# TRANSLATOR_8CH.net
KiCad netlist of a schematic drawn in Altium Designer
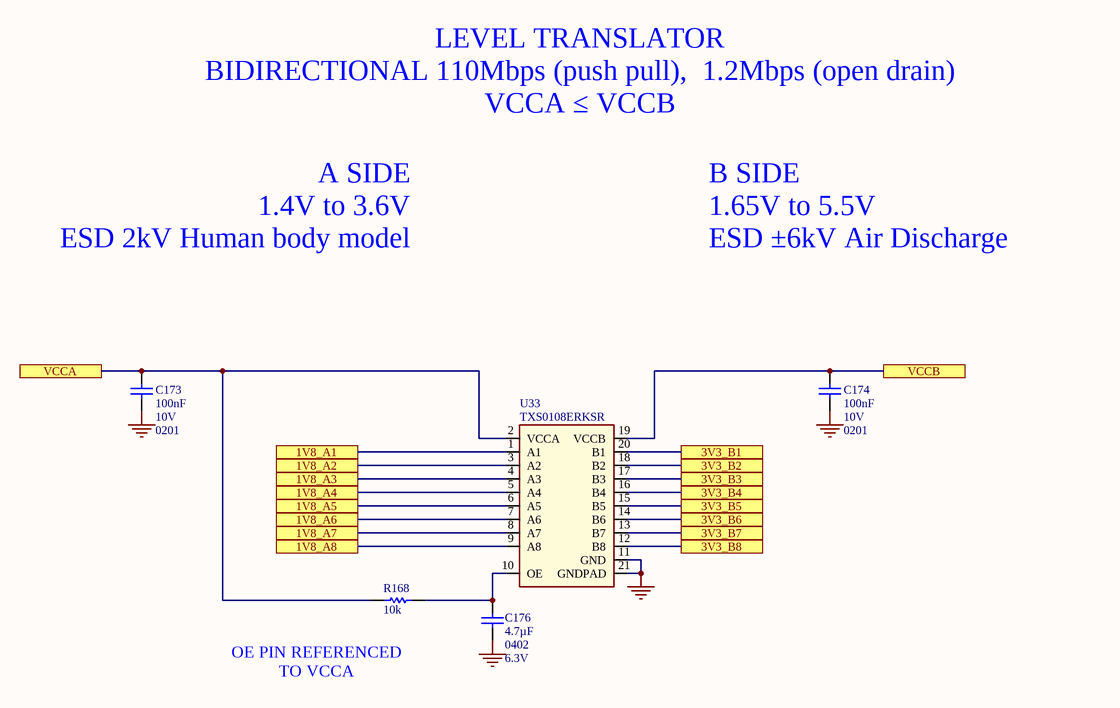
[diagram p0: TRANSLATOR_8CH.SchDoc]

(export (version "E")
  (design (tool "Eeschema 10.0.6"))
  (components
    (comp (ref "C173")
      (value "100nF")
      (footprint "CAP-0201")
      (description "CAP CHIP 0201 100nF 10% 10V X5R")
      (fields
        (field (name "PART NUMBER") "CL03A104KP3NNNC")
        (field (name "MANUFACTURER") "Samsung Electro-Mechanics")
        (field (name "VOLTAGE") "10V")
        (field (name "CASE CODE (IMPERIAL)") "0201")
      )
      (libsource (lib "Clean") (part "CAP"))
    )
    (comp (ref "C174")
      (value "100nF")
      (footprint "CAP-0201")
      (description "CAP CHIP 0201 100nF 10% 10V X5R")
      (fields
        (field (name "PART NUMBER") "CL03A104KP3NNNC")
        (field (name "MANUFACTURER") "Samsung Electro-Mechanics")
        (field (name "VOLTAGE") "10V")
        (field (name "CASE CODE (IMPERIAL)") "0201")
      )
      (libsource (lib "Clean") (part "CAP"))
    )
    (comp (ref "C176")
      (value "4.7µF")
      (footprint "CAP-0402")
      (description "CAP CHIP 0402 4.7uF 20% 6V3 X5R")
      (fields
        (field (name "MANUFACTURER") "Hottech")
        (field (name "PART NUMBER") "C1005A475M6R3NT")
        (field (name "CASE CODE (IMPERIAL)") "0402")
        (field (name "VOLTAGE") "6.3V")
      )
      (libsource (lib "Clean") (part "CAP"))
    )
    (comp (ref "R168")
      (value "10k")
      (footprint "RES-0201")
      (description "RES CHIP 0201 10k 1% 1/20W")
      (fields (field (name "POWER") "50mW") (field (name "TOLERANCE") "1%"))
      (libsource (lib "Clean") (part "RES"))
    )
    (comp (ref "U33")
      (value "TXS0108ERKSR")
      (footprint "QFN50P250X450X100_HS-21N")
      (fields (field (name "MANUFACTURER") "Texas Instruments") (field (name "LCSC PART #") "C43138309"))
      (libsource (lib "Clean") (part "TXS0108ERKSR"))
    )
  )
  (nets
    (net (code "1") (name "/1V8_A1") (class "Default")
      (node (ref "U33") (pin "1") (pinfunction "A1_1") (pintype "power_in"))
    )
    (net (code "2") (name "/1V8_A2") (class "Default")
      (node (ref "U33") (pin "3") (pinfunction "A2_3") (pintype "passive"))
    )
    (net (code "3") (name "/1V8_A3") (class "Default")
      (node (ref "U33") (pin "4") (pinfunction "A3_4") (pintype "power_in"))
    )
    (net (code "4") (name "/1V8_A4") (class "Default")
      (node (ref "U33") (pin "5") (pinfunction "A4_5") (pintype "passive"))
    )
    (net (code "5") (name "/1V8_A5") (class "Default")
      (node (ref "U33") (pin "6") (pinfunction "A5_6") (pintype "passive"))
    )
    (net (code "6") (name "/1V8_A6") (class "Default")
      (node (ref "U33") (pin "7") (pinfunction "A6_7") (pintype "passive"))
    )
    (net (code "7") (name "/1V8_A7") (class "Default")
      (node (ref "U33") (pin "8") (pinfunction "A7_8") (pintype "power_in"))
    )
    (net (code "8") (name "/1V8_A8") (class "Default")
      (node (ref "U33") (pin "9") (pinfunction "A8_9") (pintype "passive"))
    )
    (net (code "9") (name "/3V3_B1") (class "Default")
      (node (ref "U33") (pin "20") (pinfunction "B1_20") (pintype "passive"))
    )
    (net (code "10") (name "/3V3_B2") (class "Default")
      (node (ref "U33") (pin "18") (pinfunction "B2_18") (pintype "passive"))
    )
    (net (code "11") (name "/3V3_B3") (class "Default")
      (node (ref "U33") (pin "17") (pinfunction "B3_17") (pintype "passive"))
    )
    (net (code "12") (name "/3V3_B4") (class "Default")
      (node (ref "U33") (pin "16") (pinfunction "B4_16") (pintype "passive"))
    )
    (net (code "13") (name "/3V3_B5") (class "Default")
      (node (ref "U33") (pin "15") (pinfunction "B5_15") (pintype "passive"))
    )
    (net (code "14") (name "/3V3_B6") (class "Default")
      (node (ref "U33") (pin "14") (pinfunction "B6_14") (pintype "passive"))
    )
    (net (code "15") (name "/3V3_B7") (class "Default")
      (node (ref "U33") (pin "13") (pinfunction "B7_13") (pintype "passive"))
    )
    (net (code "16") (name "/3V3_B8") (class "Default")
      (node (ref "U33") (pin "12") (pinfunction "B8_12") (pintype "passive"))
    )
    (net (code "17") (name "/VCCA") (class "Default")
      (node (ref "C173") (pin "2") (pinfunction "2_2") (pintype "passive"))
      (node (ref "R168") (pin "2") (pinfunction "2_2") (pintype "passive"))
      (node (ref "U33") (pin "2") (pinfunction "VCCA_2") (pintype "passive"))
    )
    (net (code "18") (name "/VCCB") (class "Default")
      (node (ref "C174") (pin "2") (pinfunction "2_2") (pintype "passive"))
      (node (ref "U33") (pin "19") (pinfunction "VCCB_19") (pintype "passive"))
    )
    (net (code "19") (name "GND") (class "Default")
      (node (ref "C173") (pin "1") (pinfunction "1_1") (pintype "passive"))
      (node (ref "C174") (pin "1") (pinfunction "1_1") (pintype "passive"))
      (node (ref "C176") (pin "2") (pinfunction "2_2") (pintype "passive"))
      (node (ref "U33") (pin "11") (pinfunction "GND_11") (pintype "passive"))
      (node (ref "U33") (pin "21") (pinfunction "GNDPAD_21") (pintype "passive"))
    )
    (net (code "20") (name "Net-(U33-OE)") (class "Default")
      (node (ref "C176") (pin "1") (pinfunction "1_1") (pintype "passive"))
      (node (ref "R168") (pin "1") (pinfunction "1_1") (pintype "passive"))
      (node (ref "U33") (pin "10") (pinfunction "OE_10") (pintype "passive"))
    )
  )
)
